# PLL.net
KiCad netlist of a schematic drawn in Altium Designer
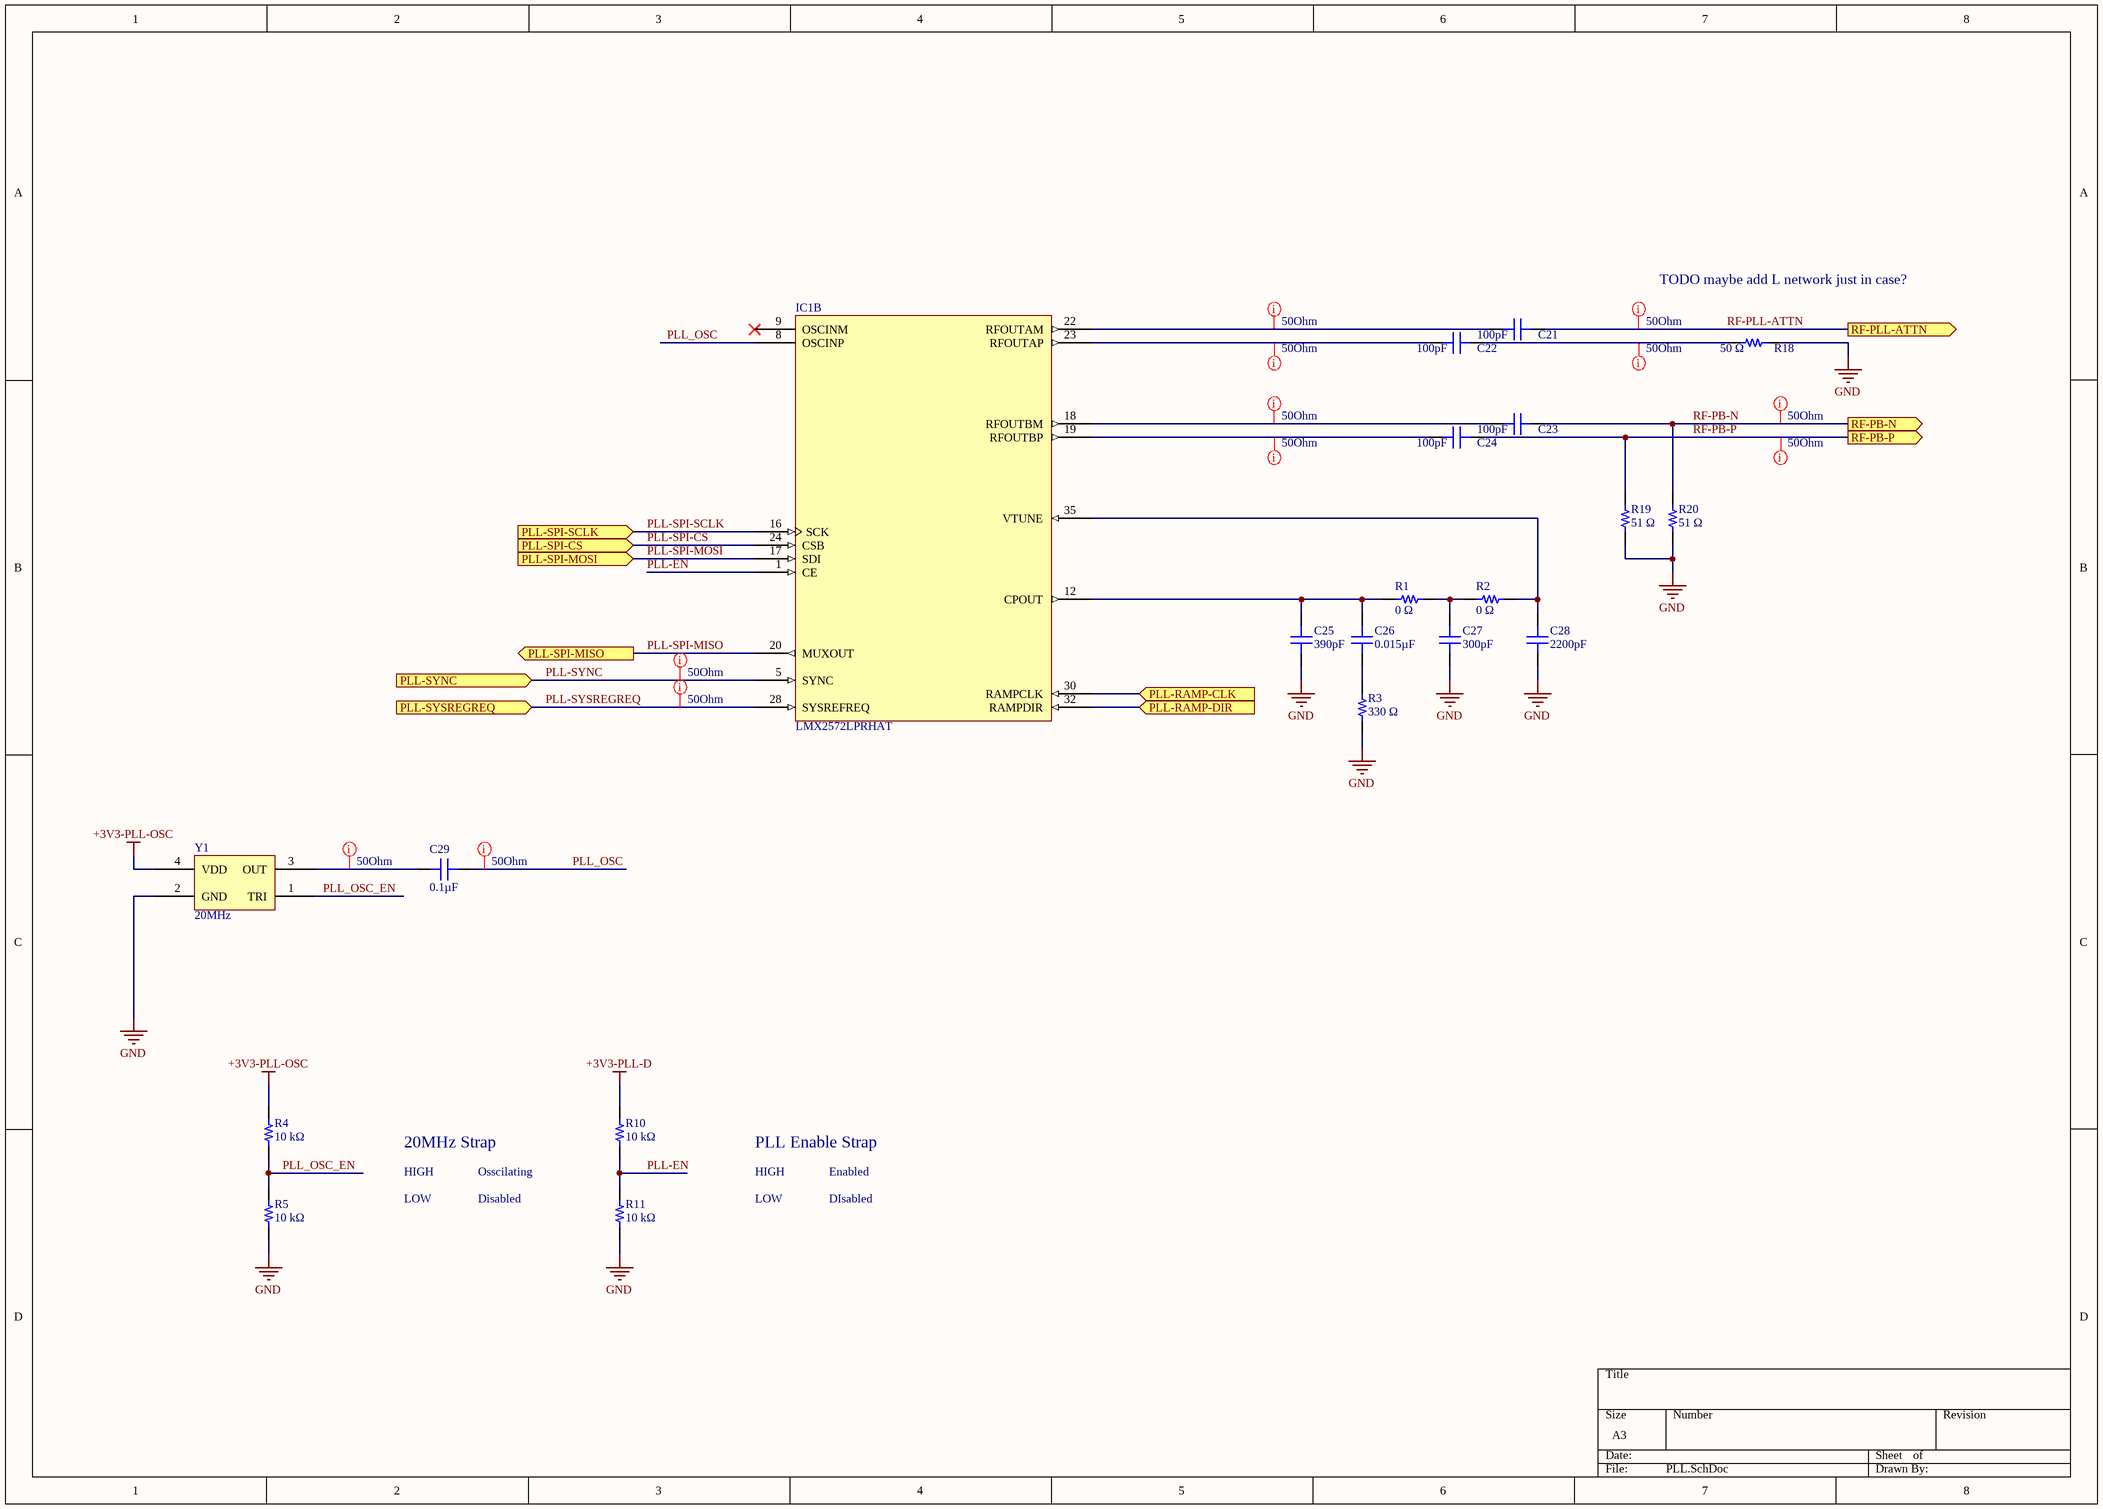
[diagram p0: PLL.SchDoc]

(export (version "E")
  (design (tool "Eeschema 10.0.6"))
  (components
    (comp (ref "C21")
      (value "100pF")
      (footprint "CAP 0402_1005 RF")
      (description "CAP CER 100PF 25V C0G/NP0 0402")
      (fields (field (name "PART NUMBER") "CBR04C101F3GAC") (field (name "MANUFACTURER") "KEMET"))
      (libsource (lib "Generic Altium Database") (part "Capacitor"))
    )
    (comp (ref "C22")
      (value "100pF")
      (footprint "CAP 0402_1005 RF")
      (description "CAP CER 100PF 25V C0G/NP0 0402")
      (fields (field (name "PART NUMBER") "CBR04C101F3GAC") (field (name "MANUFACTURER") "KEMET"))
      (libsource (lib "Generic Altium Database") (part "Capacitor"))
    )
    (comp (ref "C23")
      (value "100pF")
      (footprint "CAP 0402_1005 RF")
      (description "CAP CER 100PF 25V C0G/NP0 0402")
      (fields (field (name "PART NUMBER") "CBR04C101F3GAC") (field (name "MANUFACTURER") "KEMET"))
      (libsource (lib "Generic Altium Database") (part "Capacitor"))
    )
    (comp (ref "C24")
      (value "100pF")
      (footprint "CAP 0402_1005 RF")
      (description "CAP CER 100PF 25V C0G/NP0 0402")
      (fields (field (name "PART NUMBER") "CBR04C101F3GAC") (field (name "MANUFACTURER") "KEMET"))
      (libsource (lib "Generic Altium Database") (part "Capacitor"))
    )
    (comp (ref "C25")
      (value "390pF")
      (footprint "CAP 0402_1005")
      (description "CAP CER 390PF 50V X7R 0402")
      (fields
        (field (name "PART NUMBER") "0402B391K500CT")
        (field (name "MANUFACTURER") "Walsin Technology Corporation")
      )
      (libsource (lib "Generic Altium Database") (part "Capacitor"))
    )
    (comp (ref "C26")
      (value "0.015µF")
      (footprint "CAP 0402_1005")
      (description "CAP CER 0.015UF 16V X7R 0402")
      (fields (field (name "PART NUMBER") "0402YC153JAT2A") (field (name "MANUFACTURER") "AVX Corporation"))
      (libsource (lib "Generic Altium Database") (part "Capacitor"))
    )
    (comp (ref "C27")
      (value "300pF")
      (footprint "CAP 0402_1005")
      (description "CAP CER 300PF 50V X7R 0402")
      (fields (field (name "PART NUMBER") "CC0402KRX7R9BB301") (field (name "MANUFACTURER") "Yageo"))
      (libsource (lib "Generic Altium Database") (part "Capacitor"))
    )
    (comp (ref "C28")
      (value "2200pF")
      (footprint "CAP 0402_1005")
      (description "CAP, MLCC, 0402/1005, 16V, X7R,")
      (fields (field (name "PART NUMBER") "EMF105B7222KVHF") (field (name "MANUFACTURER") "Taiyo Yuden"))
      (libsource (lib "Generic Altium Database") (part "Capacitor"))
    )
    (comp (ref "C29")
      (value "0.1µF")
      (footprint "CAP 0805_2012 RF")
      (description "CAP CER 0.1UF 10V 0805")
      (fields (field (name "PART NUMBER") "LMK212SD104JG-T") (field (name "MANUFACTURER") "Taiyo Yuden"))
      (libsource (lib "Generic Altium Database") (part "Capacitor"))
    )
    (comp (ref "IC1")
      (value "LMX2572LPRHAT")
      (footprint "TI VQFN-40 6X6MM")
      (description "IC FREQUENCY SYNTH 40VQFN")
      (fields (field (name "MANUFACTURER") "Texas Instruments"))
      (libsource (lib "Generic Altium Database") (part "TI LMX2572"))
    )
    (comp (ref "R1")
      (value "0 Ω")
      (footprint "RES 0402_1005")
      (description "RES SMD 0 OHM JUMPER 1/16W 0402")
      (fields (field (name "PART NUMBER") "RCA04020000ZSED") (field (name "MANUFACTURER") "Vishay Dale"))
      (libsource (lib "Generic Altium Database") (part "Resistor"))
    )
    (comp (ref "R2")
      (value "0 Ω")
      (footprint "RES 0402_1005")
      (description "RES SMD 0 OHM JUMPER 1/16W 0402")
      (fields (field (name "PART NUMBER") "RCA04020000ZSED") (field (name "MANUFACTURER") "Vishay Dale"))
      (libsource (lib "Generic Altium Database") (part "Resistor"))
    )
    (comp (ref "R3")
      (value "330 Ω")
      (footprint "RES 0402_1005")
      (description "RES SMD 330 OHM 1% 1/16W 0402")
      (fields (field (name "PART NUMBER") "CR0402-FX-3300GLF") (field (name "MANUFACTURER") "Bourns Inc."))
      (libsource (lib "Generic Altium Database") (part "Resistor"))
    )
    (comp (ref "R4")
      (value "10 kΩ")
      (footprint "RES 0402_1005")
      (description "RES 10 KOHM 1% 1/16W 0402")
      (fields (field (name "PART NUMBER") "ASC0402-10KF1") (field (name "MANUFACTURER") "Riedon"))
      (libsource (lib "Generic Altium Database") (part "Resistor"))
    )
    (comp (ref "R5")
      (value "10 kΩ")
      (footprint "RES 0402_1005")
      (description "RES 10 KOHM 1% 1/16W 0402")
      (fields (field (name "PART NUMBER") "ASC0402-10KF1") (field (name "MANUFACTURER") "Riedon"))
      (libsource (lib "Generic Altium Database") (part "Resistor"))
    )
    (comp (ref "R10")
      (value "10 kΩ")
      (footprint "RES 0402_1005")
      (description "RES 10 KOHM 1% 1/16W 0402")
      (fields (field (name "PART NUMBER") "ASC0402-10KF1") (field (name "MANUFACTURER") "Riedon"))
      (libsource (lib "Generic Altium Database") (part "Resistor"))
    )
    (comp (ref "R11")
      (value "10 kΩ")
      (footprint "RES 0402_1005")
      (description "RES 10 KOHM 1% 1/16W 0402")
      (fields (field (name "PART NUMBER") "ASC0402-10KF1") (field (name "MANUFACTURER") "Riedon"))
      (libsource (lib "Generic Altium Database") (part "Resistor"))
    )
    (comp (ref "R18")
      (value "50 Ω")
      (footprint "RES 0603_1608")
      (description "RES SMD 50 OHM 2% 1.5W 0603")
      (fields (field (name "PART NUMBER") "RCP0603W50R0GEB") (field (name "MANUFACTURER") "Vishay Dale"))
      (libsource (lib "Generic Altium Database") (part "Resistor"))
    )
    (comp (ref "R19")
      (value "51 Ω")
      (footprint "RES 0402_1005")
      (description "RES SMD 51 OHM 1% 1/5W 0402")
      (fields
        (field (name "PART NUMBER") "ERJ-PA2F51R0X")
        (field (name "MANUFACTURER") "Panasonic Electronic Components")
      )
      (libsource (lib "Generic Altium Database") (part "Resistor"))
    )
    (comp (ref "R20")
      (value "51 Ω")
      (footprint "RES 0402_1005")
      (description "RES SMD 51 OHM 1% 1/5W 0402")
      (fields
        (field (name "PART NUMBER") "ERJ-PA2F51R0X")
        (field (name "MANUFACTURER") "Panasonic Electronic Components")
      )
      (libsource (lib "Generic Altium Database") (part "Resistor"))
    )
    (comp (ref "Y1")
      (value "20MHz")
      (footprint "ABRACON ASE")
      (description "XTAL OSC XO 20.0000MHZ CMOS SMD")
      (fields (field (name "PART NUMBER") "ASE-20.000MHZ-ET") (field (name "MANUFACTURER") "Abracon LLC"))
      (libsource (lib "Generic Altium Database") (part "Abracon XO ASE"))
    )
  )
  (nets
    (net (code "1") (name "+3V3-PLL-D") (class "Default")
      (node (ref "R10") (pin "2") (pinfunction "2_2") (pintype "passive"))
    )
    (net (code "2") (name "+3V3-PLL-OSC") (class "Default")
      (node (ref "R4") (pin "2") (pinfunction "2_2") (pintype "passive"))
      (node (ref "Y1") (pin "4") (pinfunction "VDD_4") (pintype "passive"))
    )
    (net (code "3") (name "/PLL-EN") (class "Default")
      (node (ref "IC1") (pin "1") (pinfunction "CE_1") (pintype "input"))
      (node (ref "R10") (pin "1") (pinfunction "1_1") (pintype "passive"))
      (node (ref "R11") (pin "2") (pinfunction "2_2") (pintype "passive"))
    )
    (net (code "4") (name "/PLL-RAMP-CLK") (class "Default")
      (node (ref "IC1") (pin "30") (pinfunction "RAMPCLK_30") (pintype "input"))
    )
    (net (code "5") (name "/PLL-RAMP-DIR") (class "Default")
      (node (ref "IC1") (pin "32") (pinfunction "RAMPDIR_32") (pintype "input"))
    )
    (net (code "6") (name "/PLL-SPI-CS") (class "Default")
      (node (ref "IC1") (pin "24") (pinfunction "CSB_24") (pintype "input"))
    )
    (net (code "7") (name "/PLL-SPI-MISO") (class "Default")
      (node (ref "IC1") (pin "20") (pinfunction "MUXOUT_20") (pintype "output"))
    )
    (net (code "8") (name "/PLL-SPI-MOSI") (class "Default")
      (node (ref "IC1") (pin "17") (pinfunction "SDI_17") (pintype "input"))
    )
    (net (code "9") (name "/PLL-SPI-SCLK") (class "Default")
      (node (ref "IC1") (pin "16") (pinfunction "SCK_16") (pintype "input"))
    )
    (net (code "10") (name "/PLL-SYNC") (class "Default")
      (node (ref "IC1") (pin "5") (pinfunction "SYNC_5") (pintype "input"))
    )
    (net (code "11") (name "/PLL-SYSREGREQ") (class "Default")
      (node (ref "IC1") (pin "28") (pinfunction "SYSREFREQ_28") (pintype "input"))
    )
    (net (code "12") (name "/PLL_OSC") (class "Default")
      (node (ref "C29") (pin "1") (pinfunction "1_1") (pintype "passive"))
      (node (ref "IC1") (pin "8") (pinfunction "OSCINP_8") (pintype "power_in"))
    )
    (net (code "13") (name "/PLL_OSC_EN") (class "Default")
      (node (ref "R4") (pin "1") (pinfunction "1_1") (pintype "passive"))
      (node (ref "R5") (pin "2") (pinfunction "2_2") (pintype "passive"))
      (node (ref "Y1") (pin "1") (pinfunction "TRI_1") (pintype "passive"))
    )
    (net (code "14") (name "/RF-PB-N") (class "Default")
      (node (ref "C23") (pin "1") (pinfunction "1_1") (pintype "passive"))
      (node (ref "R20") (pin "2") (pinfunction "2_2") (pintype "passive"))
    )
    (net (code "15") (name "/RF-PB-P") (class "Default")
      (node (ref "C24") (pin "1") (pinfunction "1_1") (pintype "passive"))
      (node (ref "R19") (pin "2") (pinfunction "2_2") (pintype "passive"))
    )
    (net (code "16") (name "/RF-PLL-ATTN") (class "Default")
      (node (ref "C21") (pin "1") (pinfunction "1_1") (pintype "passive"))
    )
    (net (code "17") (name "GND") (class "Default")
      (node (ref "C25") (pin "1") (pinfunction "1_1") (pintype "passive"))
      (node (ref "C27") (pin "1") (pinfunction "1_1") (pintype "passive"))
      (node (ref "C28") (pin "1") (pinfunction "1_1") (pintype "passive"))
      (node (ref "R11") (pin "1") (pinfunction "1_1") (pintype "passive"))
      (node (ref "R18") (pin "1") (pinfunction "1_1") (pintype "passive"))
      (node (ref "R19") (pin "1") (pinfunction "1_1") (pintype "passive"))
      (node (ref "R20") (pin "1") (pinfunction "1_1") (pintype "passive"))
      (node (ref "R3") (pin "1") (pinfunction "1_1") (pintype "passive"))
      (node (ref "R5") (pin "1") (pinfunction "1_1") (pintype "passive"))
      (node (ref "Y1") (pin "2") (pinfunction "GND_2") (pintype "passive"))
    )
    (net (code "18") (name "Net-(C22-Pad1)") (class "Default")
      (node (ref "C22") (pin "1") (pinfunction "1_1") (pintype "passive"))
      (node (ref "R18") (pin "2") (pinfunction "2_2") (pintype "passive"))
    )
    (net (code "19") (name "Net-(C26-Pad1)") (class "Default")
      (node (ref "C26") (pin "1") (pinfunction "1_1") (pintype "passive"))
      (node (ref "R3") (pin "2") (pinfunction "2_2") (pintype "passive"))
    )
    (net (code "20") (name "Net-(C27-Pad2)") (class "Default")
      (node (ref "C27") (pin "2") (pinfunction "2_2") (pintype "passive"))
      (node (ref "R1") (pin "1") (pinfunction "1_1") (pintype "passive"))
      (node (ref "R2") (pin "2") (pinfunction "2_2") (pintype "passive"))
    )
    (net (code "21") (name "Net-(IC1B-CPOUT)") (class "Default")
      (node (ref "C25") (pin "2") (pinfunction "2_2") (pintype "passive"))
      (node (ref "C26") (pin "2") (pinfunction "2_2") (pintype "passive"))
      (node (ref "IC1") (pin "12") (pinfunction "CPOUT_12") (pintype "output"))
      (node (ref "R1") (pin "2") (pinfunction "2_2") (pintype "passive"))
    )
    (net (code "22") (name "Net-(IC1B-RFOUTAM)") (class "Default")
      (node (ref "C21") (pin "2") (pinfunction "2_2") (pintype "passive"))
      (node (ref "IC1") (pin "22") (pinfunction "RFOUTAM_22") (pintype "output"))
    )
    (net (code "23") (name "Net-(IC1B-RFOUTAP)") (class "Default")
      (node (ref "C22") (pin "2") (pinfunction "2_2") (pintype "passive"))
      (node (ref "IC1") (pin "23") (pinfunction "RFOUTAP_23") (pintype "output"))
    )
    (net (code "24") (name "Net-(IC1B-RFOUTBM)") (class "Default")
      (node (ref "C23") (pin "2") (pinfunction "2_2") (pintype "passive"))
      (node (ref "IC1") (pin "18") (pinfunction "RFOUTBM_18") (pintype "output"))
    )
    (net (code "25") (name "Net-(IC1B-RFOUTBP)") (class "Default")
      (node (ref "C24") (pin "2") (pinfunction "2_2") (pintype "passive"))
      (node (ref "IC1") (pin "19") (pinfunction "RFOUTBP_19") (pintype "output"))
    )
    (net (code "26") (name "Net-(IC1B-VTUNE)") (class "Default")
      (node (ref "C28") (pin "2") (pinfunction "2_2") (pintype "passive"))
      (node (ref "IC1") (pin "35") (pinfunction "VTUNE_35") (pintype "input"))
      (node (ref "R2") (pin "1") (pinfunction "1_1") (pintype "passive"))
    )
    (net (code "27") (name "Net-(Y1-OUT)") (class "Default")
      (node (ref "C29") (pin "2") (pinfunction "2_2") (pintype "passive"))
      (node (ref "Y1") (pin "3") (pinfunction "OUT_3") (pintype "passive"))
    )
    (net (code "28") (name "unconnected-(IC1B-OSCINM-Pad9)") (class "Default")
      (node (ref "IC1") (pin "9") (pinfunction "OSCINM_9") (pintype "power_in+no_connect"))
    )
  )
)
